# rfIMUv2.net
KiCad netlist of a schematic drawn in EAGLE
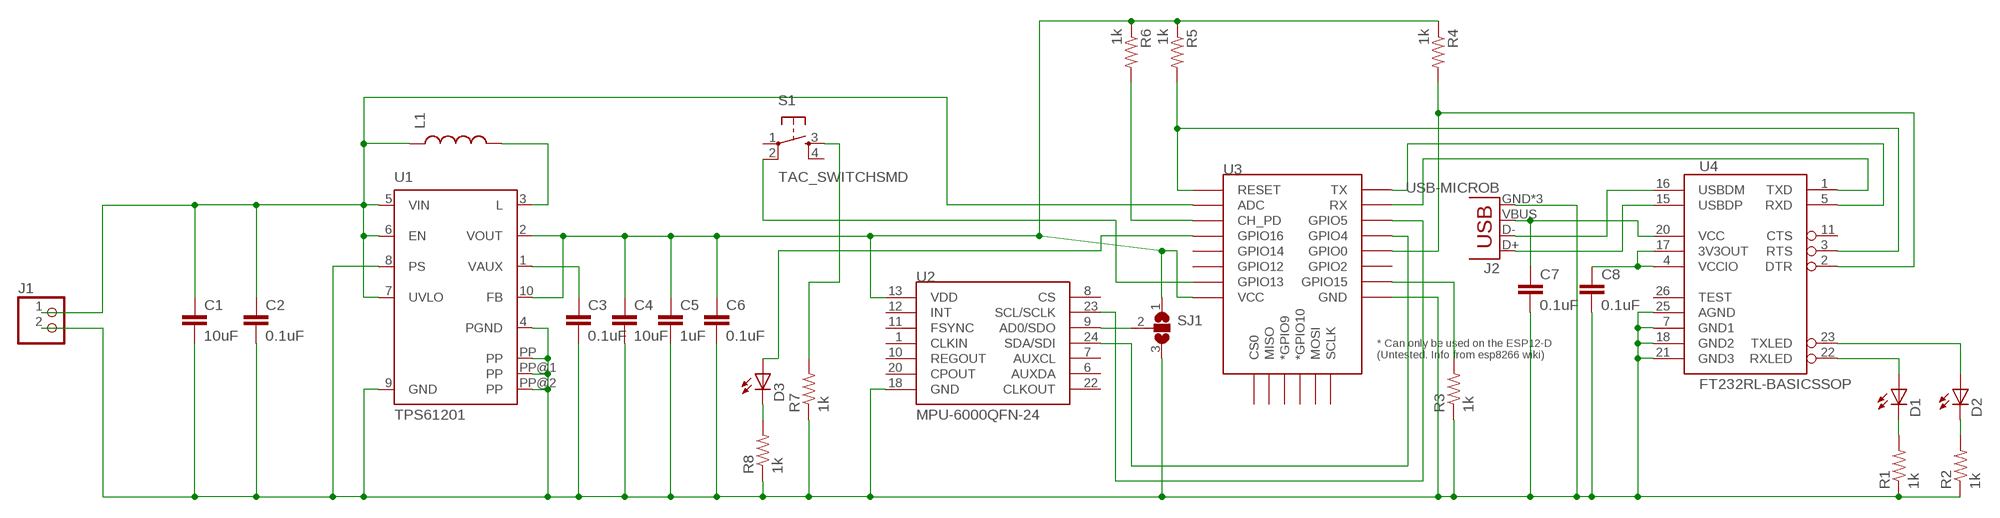
[diagram p0: schematic, sheet 1]

(export (version "E")
  (design (tool "Eeschema 10.0.6"))
  (components
    (comp (ref "C1")
      (value "10uF")
      (footprint "eagle-import:C0603")
      (libsource (lib "eagle-import") (part "C-EUC0603"))
    )
    (comp (ref "C2")
      (value "0.1uF")
      (footprint "eagle-import:C0603")
      (libsource (lib "eagle-import") (part "C-EUC0603"))
    )
    (comp (ref "C3")
      (value "0.1uF")
      (footprint "eagle-import:C0603")
      (libsource (lib "eagle-import") (part "C-EUC0603"))
    )
    (comp (ref "C4")
      (value "10uF")
      (footprint "eagle-import:C0603")
      (libsource (lib "eagle-import") (part "C-EUC0603"))
    )
    (comp (ref "C5")
      (value "1uF")
      (footprint "eagle-import:C0603")
      (libsource (lib "eagle-import") (part "C-EUC0603"))
    )
    (comp (ref "C6")
      (value "0.1uF")
      (footprint "eagle-import:C0603")
      (libsource (lib "eagle-import") (part "C-EUC0603"))
    )
    (comp (ref "C7")
      (value "0.1uF")
      (footprint "eagle-import:C0603")
      (libsource (lib "eagle-import") (part "C-EUC0603"))
    )
    (comp (ref "C8")
      (value "0.1uF")
      (footprint "eagle-import:C0603")
      (libsource (lib "eagle-import") (part "C-EUC0603"))
    )
    (comp (ref "D1")
      (value "LEDCHIPLED_0603")
      (footprint "eagle-import:CHIPLED_0603")
      (libsource (lib "eagle-import") (part "LEDCHIPLED_0603"))
    )
    (comp (ref "D2")
      (value "LEDCHIPLED_0603")
      (footprint "eagle-import:CHIPLED_0603")
      (libsource (lib "eagle-import") (part "LEDCHIPLED_0603"))
    )
    (comp (ref "D3")
      (value "LEDCHIP-LED0603")
      (footprint "eagle-import:CHIP-LED0603")
      (libsource (lib "eagle-import") (part "LEDCHIP-LED0603"))
    )
    (comp (ref "J1")
      (value "PINHD-1X2")
      (footprint "eagle-import:1X02")
      (libsource (lib "eagle-import") (part "PINHD-1X2"))
    )
    (comp (ref "J2")
      (value "USB-MICROB")
      (footprint "eagle-import:USB-MICROB")
      (libsource (lib "eagle-import") (part "USB-MICROB"))
    )
    (comp (ref "L1")
      (value "INDUCTOR0805")
      (footprint "eagle-import:0805")
      (libsource (lib "eagle-import") (part "INDUCTOR0805"))
    )
    (comp (ref "R1")
      (value "1k")
      (footprint "eagle-import:R0603")
      (libsource (lib "eagle-import") (part "R-US_R0603"))
    )
    (comp (ref "R2")
      (value "1k")
      (footprint "eagle-import:R0603")
      (libsource (lib "eagle-import") (part "R-US_R0603"))
    )
    (comp (ref "R3")
      (value "1k")
      (footprint "eagle-import:R0603")
      (libsource (lib "eagle-import") (part "R-US_R0603"))
    )
    (comp (ref "R4")
      (value "1k")
      (footprint "eagle-import:R0603")
      (libsource (lib "eagle-import") (part "R-US_R0603"))
    )
    (comp (ref "R5")
      (value "1k")
      (footprint "eagle-import:R0603")
      (libsource (lib "eagle-import") (part "R-US_R0603"))
    )
    (comp (ref "R6")
      (value "1k")
      (footprint "eagle-import:R0603")
      (libsource (lib "eagle-import") (part "R-US_R0603"))
    )
    (comp (ref "R7")
      (value "1k")
      (footprint "eagle-import:R0603")
      (libsource (lib "eagle-import") (part "R-US_R0603"))
    )
    (comp (ref "R8")
      (value "1k")
      (footprint "eagle-import:R0603")
      (libsource (lib "eagle-import") (part "R-US_R0603"))
    )
    (comp (ref "S1")
      (value "TAC_SWITCHSMD")
      (footprint "eagle-import:TACTILE-SWITCH-SMD")
      (libsource (lib "eagle-import") (part "TAC_SWITCHSMD"))
    )
    (comp (ref "SJ1")
      (value "SJ2W")
      (footprint "eagle-import:SJ_2")
      (libsource (lib "eagle-import") (part "SJ2W"))
    )
    (comp (ref "U1")
      (value "TPS61201")
      (footprint "eagle-import:S-PDSO-N10")
      (fields (field (name "MPN") "TPS61201DRCT"))
      (libsource (lib "eagle-import") (part "TPS61201"))
    )
    (comp (ref "U2")
      (value "MPU-6000QFN-24")
      (footprint "eagle-import:QFN-24-TESTING")
      (libsource (lib "eagle-import") (part "MPU-6000QFN-24"))
    )
    (comp (ref "U3")
      (value "ESP12ESMD")
      (footprint "eagle-import:ESP12E-SMD")
      (libsource (lib "eagle-import") (part "ESP12ESMD"))
    )
    (comp (ref "U4")
      (value "FT232RL-BASICSSOP")
      (footprint "eagle-import:SSOP28DB")
      (libsource (lib "eagle-import") (part "FT232RL-BASICSSOP"))
    )
  )
  (nets
    (net (code "1") (name "Net-(D1-PadC)") (class "Default")
      (node (ref "D1") (pin "C") (pinfunction "C_C") (pintype "passive"))
      (node (ref "R1") (pin "2") (pinfunction "2_2") (pintype "passive"))
    )
    (net (code "2") (name "Net-(D2-PadC)") (class "Default")
      (node (ref "D2") (pin "C") (pinfunction "C_C") (pintype "passive"))
      (node (ref "R2") (pin "2") (pinfunction "2_2") (pintype "passive"))
    )
    (net (code "3") (name "Net-(D3-PadA)") (class "Default")
      (node (ref "D3") (pin "A") (pinfunction "A_A") (pintype "passive"))
      (node (ref "U3") (pin "GPIO16") (pinfunction "GPIO16_GPIO16") (pintype "bidirectional"))
    )
    (net (code "4") (name "Net-(D3-PadC)") (class "Default")
      (node (ref "D3") (pin "C") (pinfunction "C_C") (pintype "passive"))
      (node (ref "R8") (pin "2") (pinfunction "2_2") (pintype "passive"))
    )
    (net (code "5") (name "Net-(R3-Pad2)") (class "Default")
      (node (ref "R3") (pin "2") (pinfunction "2_2") (pintype "passive"))
      (node (ref "U3") (pin "GPIO15") (pinfunction "GPIO15_GPIO15") (pintype "bidirectional"))
    )
    (net (code "6") (name "Net-(R6-Pad2)") (class "Default")
      (node (ref "R6") (pin "2") (pinfunction "2_2") (pintype "passive"))
      (node (ref "U3") (pin "CH_PD") (pinfunction "CH_PD_CH_PD") (pintype "bidirectional"))
    )
    (net (code "7") (name "Net-(R7-Pad2)") (class "Default")
      (node (ref "R7") (pin "2") (pinfunction "2_2") (pintype "passive"))
      (node (ref "S1") (pin "3") (pinfunction "3_3") (pintype "passive"))
    )
    (net (code "8") (name "Net-(S1-Pad2)") (class "Default")
      (node (ref "S1") (pin "2") (pinfunction "2_2") (pintype "passive"))
      (node (ref "U3") (pin "GPIO13") (pinfunction "GPIO13_GPIO13") (pintype "bidirectional"))
    )
    (net (code "9") (name "Net-(U1-EN)") (class "Default")
      (node (ref "C1") (pin "1") (pinfunction "1_1") (pintype "passive"))
      (node (ref "C2") (pin "1") (pinfunction "1_1") (pintype "passive"))
      (node (ref "J1") (pin "1") (pinfunction "1_1") (pintype "passive"))
      (node (ref "L1") (pin "1") (pinfunction "1_1") (pintype "passive"))
      (node (ref "U1") (pin "5") (pinfunction "VIN_5") (pintype "input"))
      (node (ref "U1") (pin "6") (pinfunction "EN_6") (pintype "input"))
      (node (ref "U1") (pin "7") (pinfunction "UVLO_7") (pintype "input"))
      (node (ref "U3") (pin "ADC") (pinfunction "ADC_ADC") (pintype "bidirectional"))
    )
    (net (code "10") (name "Net-(U1-FB)") (class "Default")
      (node (ref "C4") (pin "1") (pinfunction "1_1") (pintype "passive"))
      (node (ref "C5") (pin "1") (pinfunction "1_1") (pintype "passive"))
      (node (ref "C6") (pin "1") (pinfunction "1_1") (pintype "passive"))
      (node (ref "R4") (pin "1") (pinfunction "1_1") (pintype "passive"))
      (node (ref "R5") (pin "1") (pinfunction "1_1") (pintype "passive"))
      (node (ref "R6") (pin "1") (pinfunction "1_1") (pintype "passive"))
      (node (ref "SJ1") (pin "1") (pinfunction "1_1") (pintype "passive"))
      (node (ref "U1") (pin "10") (pinfunction "FB_10") (pintype "input"))
      (node (ref "U1") (pin "2") (pinfunction "VOUT_2") (pintype "passive"))
      (node (ref "U2") (pin "13") (pinfunction "VDD_13") (pintype "bidirectional"))
      (node (ref "U3") (pin "VCC") (pinfunction "VCC_VCC") (pintype "bidirectional"))
    )
    (net (code "11") (name "Net-(U1-GND)") (class "Default")
      (node (ref "C1") (pin "2") (pinfunction "2_2") (pintype "passive"))
      (node (ref "C2") (pin "2") (pinfunction "2_2") (pintype "passive"))
      (node (ref "C3") (pin "2") (pinfunction "2_2") (pintype "passive"))
      (node (ref "C4") (pin "2") (pinfunction "2_2") (pintype "passive"))
      (node (ref "C5") (pin "2") (pinfunction "2_2") (pintype "passive"))
      (node (ref "C6") (pin "2") (pinfunction "2_2") (pintype "passive"))
      (node (ref "C7") (pin "2") (pinfunction "2_2") (pintype "passive"))
      (node (ref "C8") (pin "2") (pinfunction "2_2") (pintype "passive"))
      (node (ref "J1") (pin "2") (pinfunction "2_2") (pintype "passive"))
      (node (ref "J2") (pin "GND") (pinfunction "GND_GND") (pintype "bidirectional"))
      (node (ref "J2") (pin "MT1") (pinfunction "GND_MT1") (pintype "bidirectional"))
      (node (ref "J2") (pin "MT2") (pinfunction "GND_MT2") (pintype "bidirectional"))
      (node (ref "R1") (pin "1") (pinfunction "1_1") (pintype "passive"))
      (node (ref "R2") (pin "1") (pinfunction "1_1") (pintype "passive"))
      (node (ref "R3") (pin "1") (pinfunction "1_1") (pintype "passive"))
      (node (ref "R7") (pin "1") (pinfunction "1_1") (pintype "passive"))
      (node (ref "R8") (pin "1") (pinfunction "1_1") (pintype "passive"))
      (node (ref "SJ1") (pin "3") (pinfunction "3_3") (pintype "passive"))
      (node (ref "U1") (pin "4") (pinfunction "PGND_4") (pintype "power_in"))
      (node (ref "U1") (pin "8") (pinfunction "PS_8") (pintype "input"))
      (node (ref "U1") (pin "9") (pinfunction "GND_9") (pintype "power_in"))
      (node (ref "U1") (pin "PP") (pinfunction "PP_PP") (pintype "power_in"))
      (node (ref "U1") (pin "PP@1") (pinfunction "PP_PP@1") (pintype "power_in"))
      (node (ref "U1") (pin "PP@2") (pinfunction "PP_PP@2") (pintype "power_in"))
      (node (ref "U2") (pin "18") (pinfunction "GND_18") (pintype "bidirectional"))
      (node (ref "U3") (pin "GND") (pinfunction "GND_GND") (pintype "bidirectional"))
      (node (ref "U4") (pin "18") (pinfunction "GND2_18") (pintype "power_in"))
      (node (ref "U4") (pin "21") (pinfunction "GND3_21") (pintype "power_in"))
      (node (ref "U4") (pin "25") (pinfunction "AGND_25") (pintype "power_in"))
      (node (ref "U4") (pin "7") (pinfunction "GND1_7") (pintype "power_in"))
    )
    (net (code "12") (name "Net-(U1-L)") (class "Default")
      (node (ref "L1") (pin "2") (pinfunction "2_2") (pintype "passive"))
      (node (ref "U1") (pin "3") (pinfunction "L_3") (pintype "input"))
    )
    (net (code "13") (name "Net-(U1-VAUX)") (class "Default")
      (node (ref "C3") (pin "1") (pinfunction "1_1") (pintype "passive"))
      (node (ref "U1") (pin "1") (pinfunction "VAUX_1") (pintype "bidirectional"))
    )
    (net (code "14") (name "Net-(U2-AD0{slash}SDO)") (class "Default")
      (node (ref "SJ1") (pin "2") (pinfunction "2_2") (pintype "passive"))
      (node (ref "U2") (pin "9") (pinfunction "AD0/SDO_9") (pintype "bidirectional"))
    )
    (net (code "15") (name "Net-(U2-SCL{slash}SCLK)") (class "Default")
      (node (ref "U2") (pin "23") (pinfunction "SCL/SCLK_23") (pintype "bidirectional"))
      (node (ref "U3") (pin "GPIO5") (pinfunction "GPIO5_GPIO5") (pintype "bidirectional"))
    )
    (net (code "16") (name "Net-(U2-SDA{slash}SDI)") (class "Default")
      (node (ref "U2") (pin "24") (pinfunction "SDA/SDI_24") (pintype "bidirectional"))
      (node (ref "U3") (pin "GPIO4") (pinfunction "GPIO4_GPIO4") (pintype "bidirectional"))
    )
    (net (code "17") (name "Net-(U3-RX)") (class "Default")
      (node (ref "U3") (pin "RXD0") (pinfunction "RX_RXD0") (pintype "bidirectional"))
      (node (ref "U4") (pin "1") (pinfunction "TXD_1") (pintype "output"))
    )
    (net (code "18") (name "Net-(U3-TX)") (class "Default")
      (node (ref "U3") (pin "TXD0") (pinfunction "TX_TXD0") (pintype "bidirectional"))
      (node (ref "U4") (pin "5") (pinfunction "RXD_5") (pintype "input"))
    )
    (net (code "19") (name "Net-(U4-3V3OUT)") (class "Default")
      (node (ref "C8") (pin "1") (pinfunction "1_1") (pintype "passive"))
      (node (ref "U4") (pin "17") (pinfunction "3V3OUT_17") (pintype "output"))
      (node (ref "U4") (pin "4") (pinfunction "VCCIO_4") (pintype "power_in"))
    )
    (net (code "20") (name "Net-(U4-DTR)") (class "Default")
      (node (ref "R4") (pin "2") (pinfunction "2_2") (pintype "passive"))
      (node (ref "U3") (pin "GPIO0") (pinfunction "GPIO0_GPIO0") (pintype "bidirectional"))
      (node (ref "U4") (pin "2") (pinfunction "DTR_2") (pintype "bidirectional"))
    )
    (net (code "21") (name "Net-(U4-RTS)") (class "Default")
      (node (ref "R5") (pin "2") (pinfunction "2_2") (pintype "passive"))
      (node (ref "U3") (pin "RESET") (pinfunction "RESET_RESET") (pintype "bidirectional"))
      (node (ref "U4") (pin "3") (pinfunction "RTS_3") (pintype "bidirectional"))
    )
    (net (code "22") (name "Net-(U4-RXLED)") (class "Default")
      (node (ref "D1") (pin "A") (pinfunction "A_A") (pintype "passive"))
      (node (ref "U4") (pin "22") (pinfunction "RXLED_22") (pintype "bidirectional"))
    )
    (net (code "23") (name "Net-(U4-TXLED)") (class "Default")
      (node (ref "D2") (pin "A") (pinfunction "A_A") (pintype "passive"))
      (node (ref "U4") (pin "23") (pinfunction "TXLED_23") (pintype "bidirectional"))
    )
    (net (code "24") (name "Net-(U4-USBDM)") (class "Default")
      (node (ref "J2") (pin "D-") (pinfunction "D-_D-") (pintype "bidirectional"))
      (node (ref "U4") (pin "16") (pinfunction "USBDM_16") (pintype "bidirectional"))
    )
    (net (code "25") (name "Net-(U4-USBDP)") (class "Default")
      (node (ref "J2") (pin "D+") (pinfunction "D+_D+") (pintype "bidirectional"))
      (node (ref "U4") (pin "15") (pinfunction "USBDP_15") (pintype "bidirectional"))
    )
    (net (code "26") (name "Net-(U4-VCC)") (class "Default")
      (node (ref "C7") (pin "1") (pinfunction "1_1") (pintype "passive"))
      (node (ref "J2") (pin "VBUS") (pinfunction "VBUS_VBUS") (pintype "bidirectional"))
      (node (ref "U4") (pin "20") (pinfunction "VCC_20") (pintype "power_in"))
    )
    (net (code "27") (name "unconnected-(S1-Pad1)") (class "Default")
      (node (ref "S1") (pin "1") (pinfunction "1_1") (pintype "passive"))
    )
    (net (code "28") (name "unconnected-(S1-Pad4)") (class "Default")
      (node (ref "S1") (pin "4") (pinfunction "4_4") (pintype "passive"))
    )
    (net (code "29") (name "unconnected-(U2-AUXCL-Pad7)") (class "Default")
      (node (ref "U2") (pin "7") (pinfunction "AUXCL_7") (pintype "bidirectional"))
    )
    (net (code "30") (name "unconnected-(U2-AUXDA-Pad6)") (class "Default")
      (node (ref "U2") (pin "6") (pinfunction "AUXDA_6") (pintype "bidirectional"))
    )
    (net (code "31") (name "unconnected-(U2-CLKIN-Pad1)") (class "Default")
      (node (ref "U2") (pin "1") (pinfunction "CLKIN_1") (pintype "bidirectional"))
    )
    (net (code "32") (name "unconnected-(U2-CLKOUT-Pad22)") (class "Default")
      (node (ref "U2") (pin "22") (pinfunction "CLKOUT_22") (pintype "bidirectional"))
    )
    (net (code "33") (name "unconnected-(U2-CPOUT-Pad20)") (class "Default")
      (node (ref "U2") (pin "20") (pinfunction "CPOUT_20") (pintype "bidirectional"))
    )
    (net (code "34") (name "unconnected-(U2-CS-Pad8)") (class "Default")
      (node (ref "U2") (pin "8") (pinfunction "CS_8") (pintype "bidirectional"))
    )
    (net (code "35") (name "unconnected-(U2-FSYNC-Pad11)") (class "Default")
      (node (ref "U2") (pin "11") (pinfunction "FSYNC_11") (pintype "bidirectional"))
    )
    (net (code "36") (name "unconnected-(U2-INT-Pad12)") (class "Default")
      (node (ref "U2") (pin "12") (pinfunction "INT_12") (pintype "bidirectional"))
    )
    (net (code "37") (name "unconnected-(U2-REGOUT-Pad10)") (class "Default")
      (node (ref "U2") (pin "10") (pinfunction "REGOUT_10") (pintype "bidirectional"))
    )
    (net (code "38") (name "unconnected-(U3-*GPIO9-PadGPIO9)") (class "Default")
      (node (ref "U3") (pin "GPIO9") (pinfunction "*GPIO9_GPIO9") (pintype "bidirectional"))
    )
    (net (code "39") (name "unconnected-(U3-*GPIO10-PadGPIO10)") (class "Default")
      (node (ref "U3") (pin "GPIO10") (pinfunction "*GPIO10_GPIO10") (pintype "bidirectional"))
    )
    (net (code "40") (name "unconnected-(U3-PadCS0)") (class "Default")
      (node (ref "U3") (pin "CS0") (pinfunction "CS0_CS0") (pintype "bidirectional"))
    )
    (net (code "41") (name "unconnected-(U3-PadGPIO2)") (class "Default")
      (node (ref "U3") (pin "GPIO2") (pinfunction "GPIO2_GPIO2") (pintype "bidirectional"))
    )
    (net (code "42") (name "unconnected-(U3-PadGPIO12)") (class "Default")
      (node (ref "U3") (pin "GPIO12") (pinfunction "GPIO12_GPIO12") (pintype "bidirectional"))
    )
    (net (code "43") (name "unconnected-(U3-PadGPIO14)") (class "Default")
      (node (ref "U3") (pin "GPIO14") (pinfunction "GPIO14_GPIO14") (pintype "bidirectional"))
    )
    (net (code "44") (name "unconnected-(U3-PadMISO)") (class "Default")
      (node (ref "U3") (pin "MISO") (pinfunction "MISO_MISO") (pintype "bidirectional"))
    )
    (net (code "45") (name "unconnected-(U3-PadMOSI)") (class "Default")
      (node (ref "U3") (pin "MOSI") (pinfunction "MOSI_MOSI") (pintype "bidirectional"))
    )
    (net (code "46") (name "unconnected-(U3-PadSCLK)") (class "Default")
      (node (ref "U3") (pin "SCLK") (pinfunction "SCLK_SCLK") (pintype "bidirectional"))
    )
    (net (code "47") (name "unconnected-(U4-CTS-Pad11)") (class "Default")
      (node (ref "U4") (pin "11") (pinfunction "CTS_11") (pintype "bidirectional"))
    )
    (net (code "48") (name "unconnected-(U4-TEST-Pad26)") (class "Default")
      (node (ref "U4") (pin "26") (pinfunction "TEST_26") (pintype "input"))
    )
  )
)
